# lisa_m.net
KiCad netlist of a schematic drawn in EAGLE
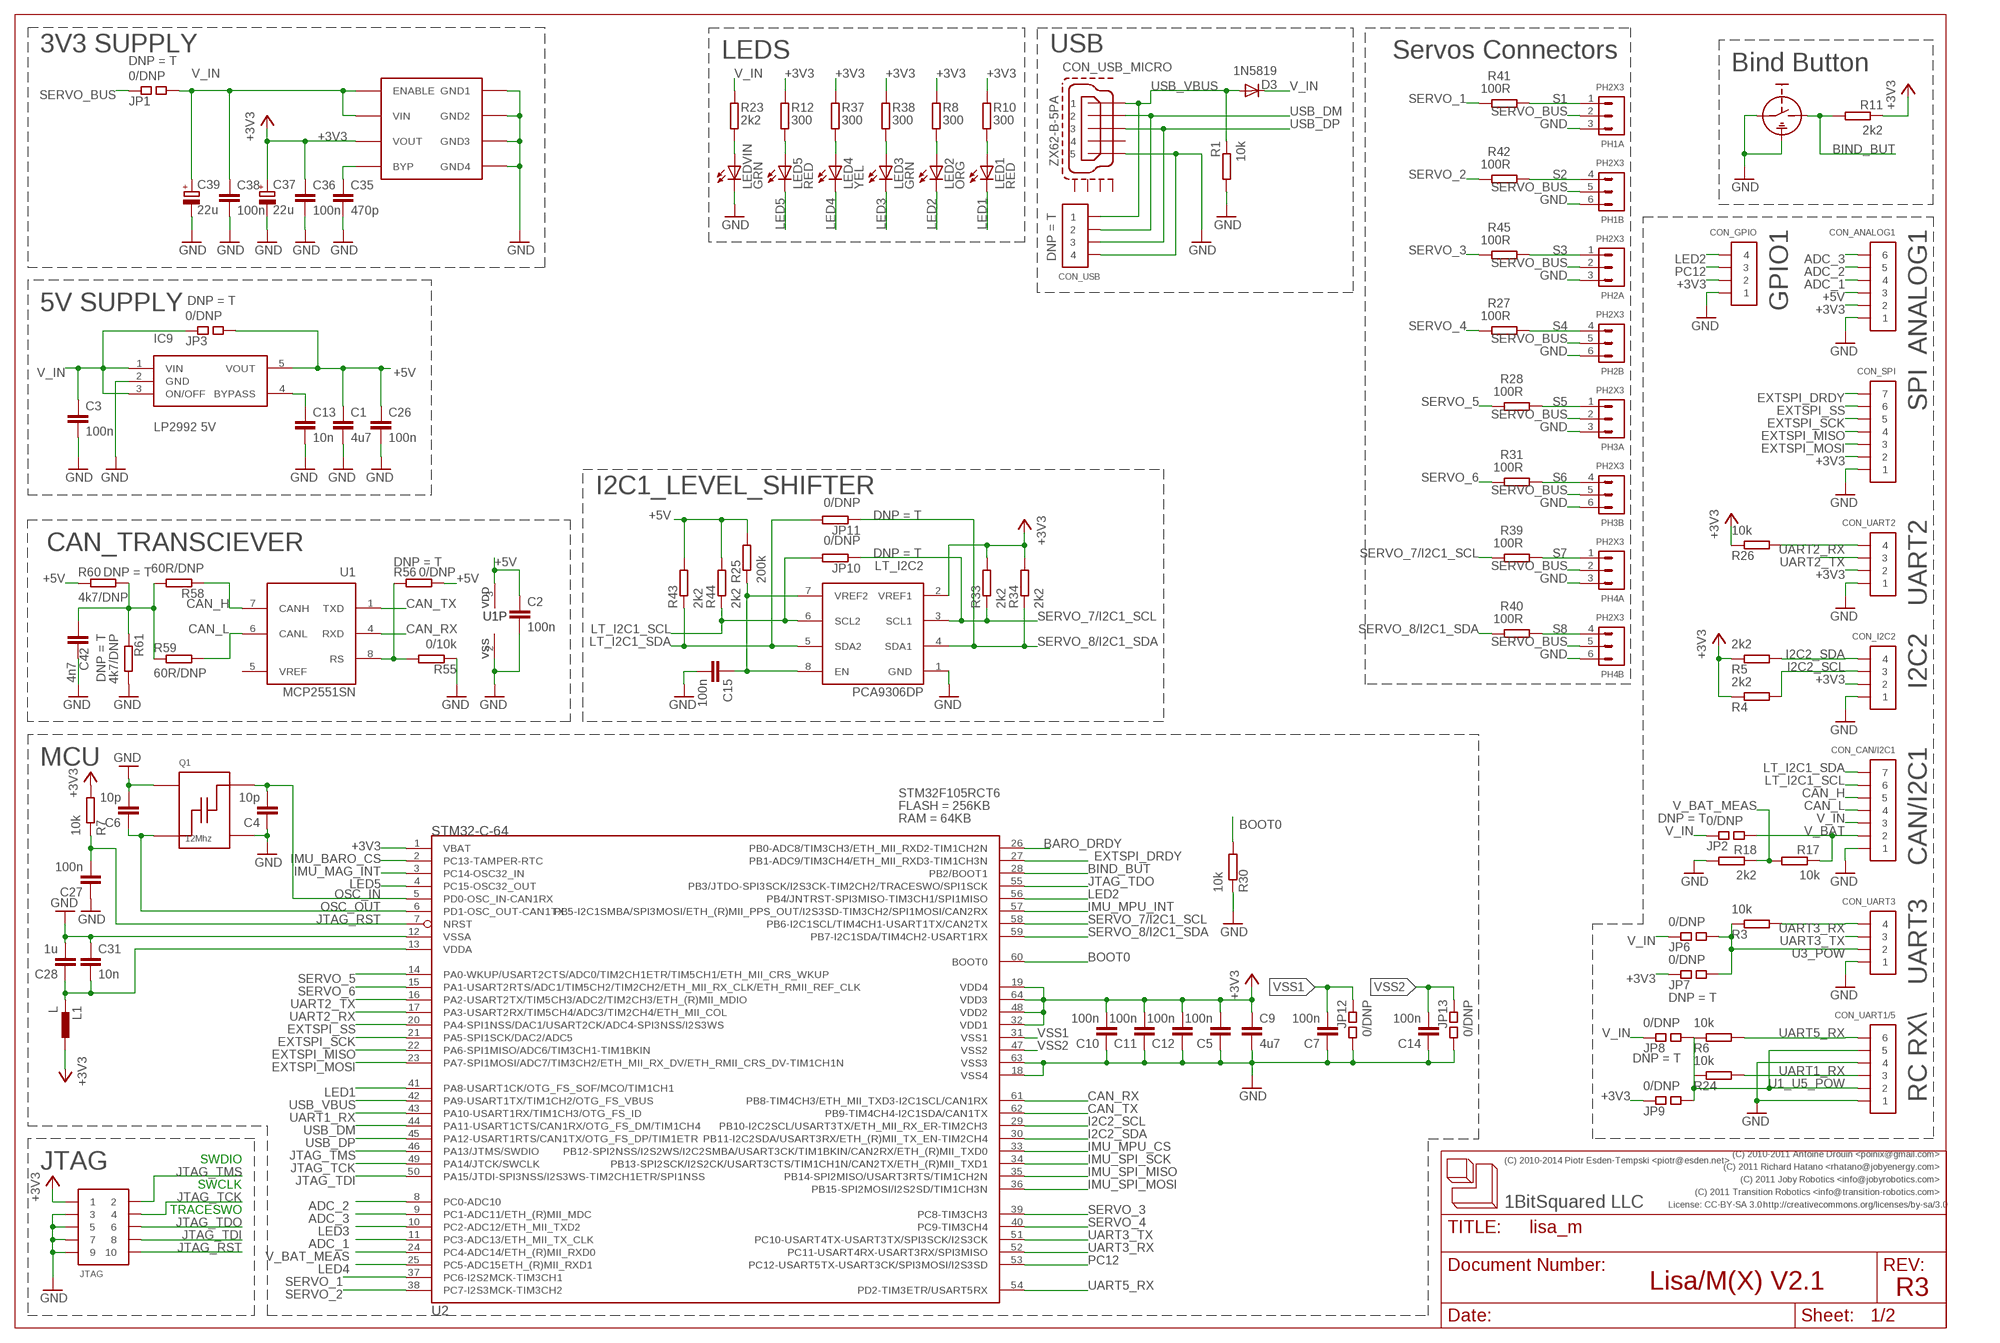
[diagram p0: schematic, sheet 1]
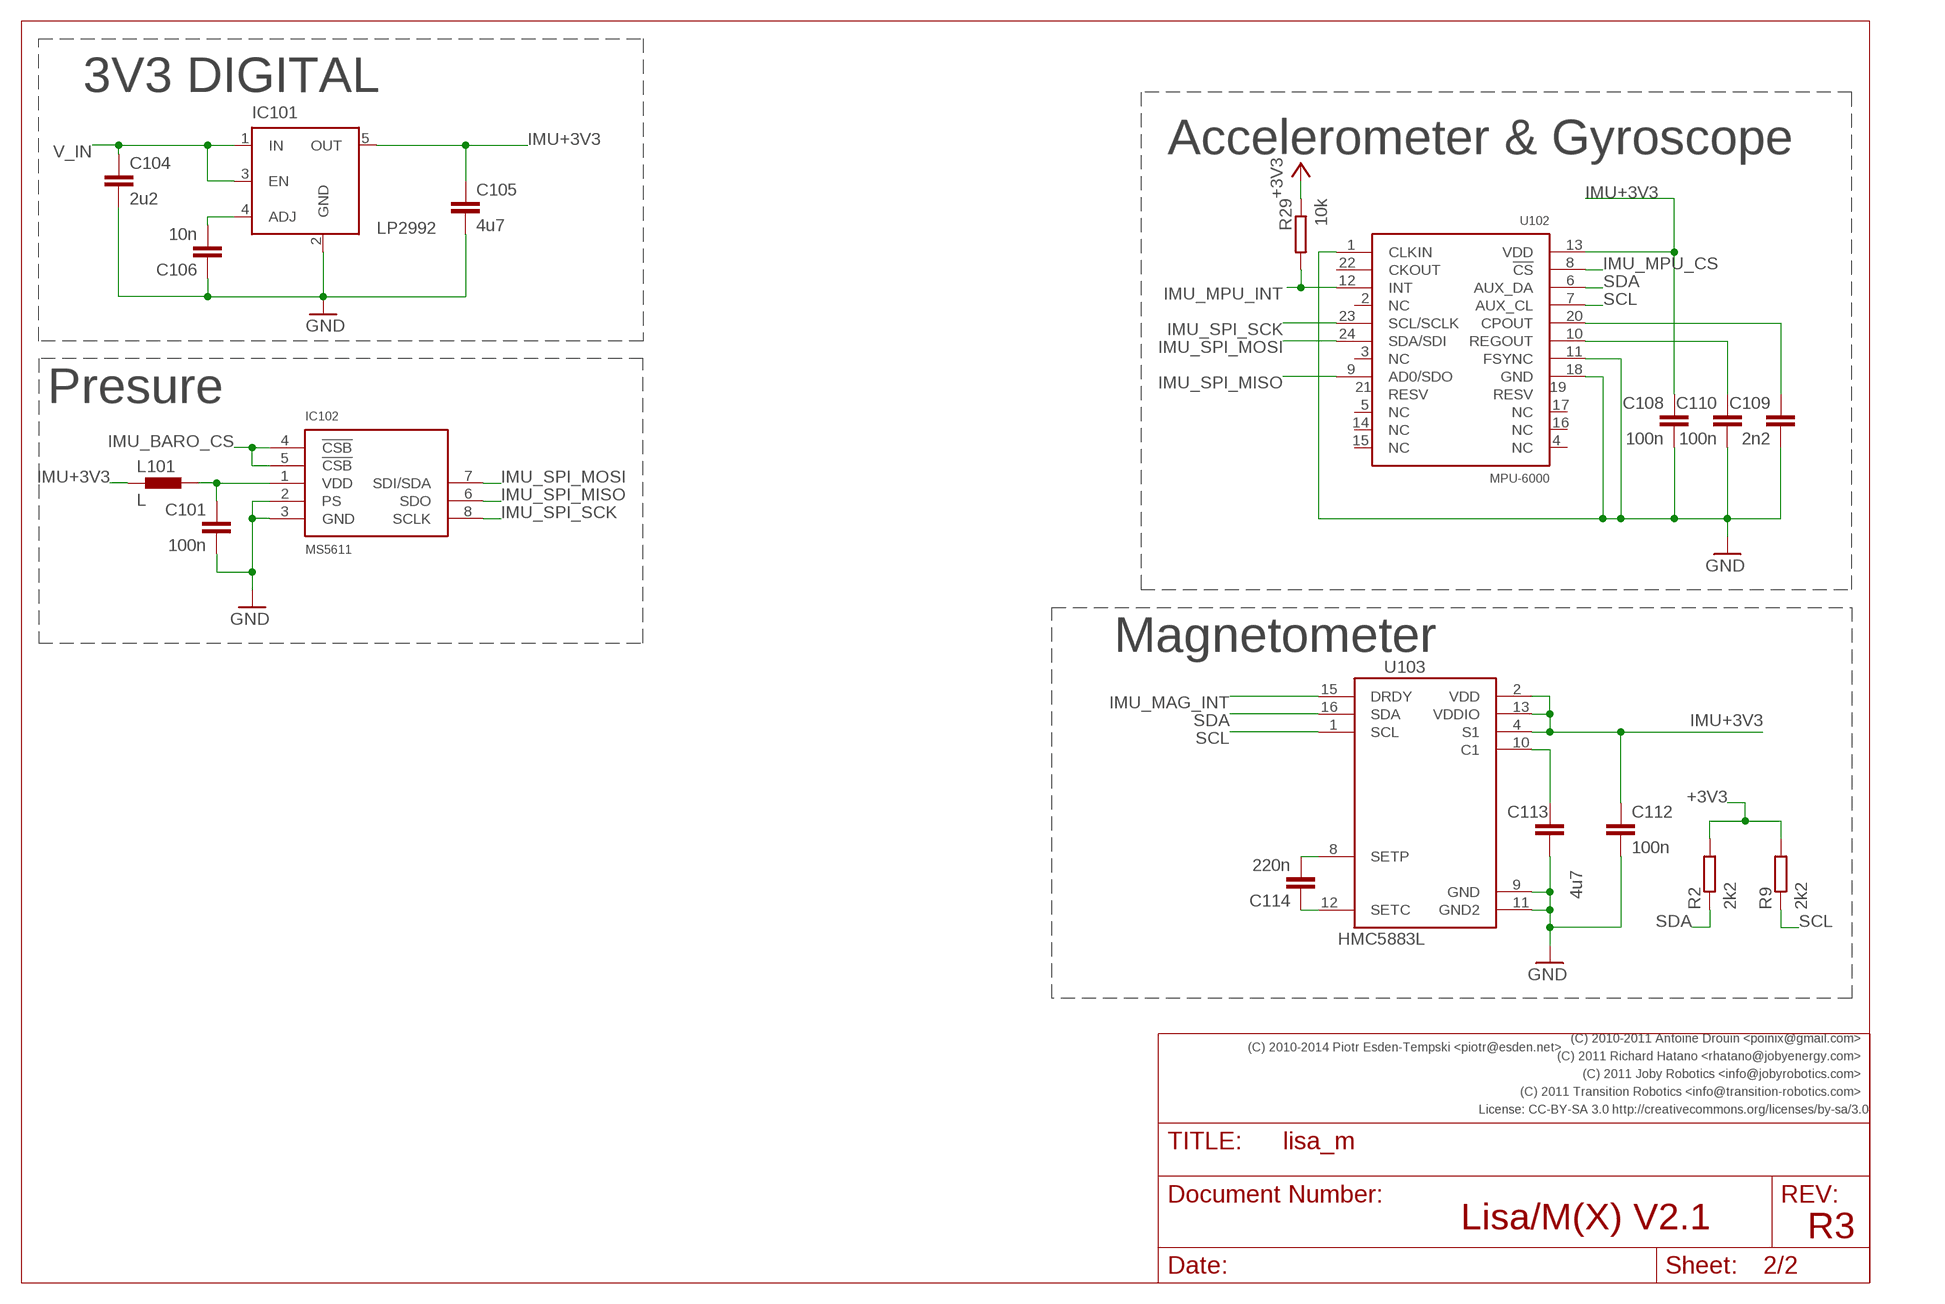
[diagram p1: schematic, sheet 2]

(export (version "E")
  (design (tool "Eeschema 10.0.6"))
  (components
    (comp (ref "C101")
      (value "100n")
      (footprint "eagle-import:0402-CAP")
      (fields (field (name "PARTNO") "cap-cer-0402-100n"))
      (libsource (lib "eagle-import") (part "CAPACITOR-0402"))
    )
    (comp (ref "C104")
      (value "2u2")
      (footprint "eagle-import:0603-CAP")
      (fields (field (name "PARTNO") "cap-cer-0603-2u2"))
      (libsource (lib "eagle-import") (part "CAPACITOR-0603"))
    )
    (comp (ref "C105")
      (value "4u7")
      (footprint "eagle-import:0603-CAP")
      (fields (field (name "PARTNO") "cap-cer-0603-4u7"))
      (libsource (lib "eagle-import") (part "CAPACITOR-0603"))
    )
    (comp (ref "C106")
      (value "10n")
      (footprint "eagle-import:0402-CAP")
      (fields (field (name "PARTNO") "cap-cer-0402-10n"))
      (libsource (lib "eagle-import") (part "CAPACITOR-0402"))
    )
    (comp (ref "C108")
      (value "100n")
      (footprint "eagle-import:0402-CAP")
      (fields (field (name "PARTNO") "cap-cer-0402-100n"))
      (libsource (lib "eagle-import") (part "CAPACITOR-0402"))
    )
    (comp (ref "C109")
      (value "2n2")
      (footprint "eagle-import:0402-CAP")
      (fields (field (name "PARTNO") "cap-cer-0402-2n2"))
      (libsource (lib "eagle-import") (part "CAPACITOR-0402"))
    )
    (comp (ref "C110")
      (value "100n")
      (footprint "eagle-import:0402-CAP")
      (fields (field (name "PARTNO") "cap-cer-0402-100n"))
      (libsource (lib "eagle-import") (part "CAPACITOR-0402"))
    )
    (comp (ref "C112")
      (value "100n")
      (footprint "eagle-import:0402-CAP")
      (fields (field (name "PARTNO") "cap-cer-0402-100n"))
      (libsource (lib "eagle-import") (part "CAPACITOR-0402"))
    )
    (comp (ref "C113")
      (value "4u7")
      (footprint "eagle-import:0603-CAP")
      (fields (field (name "PARTNO") "cap-cer-0603-4u7"))
      (libsource (lib "eagle-import") (part "CAPACITOR-0603"))
    )
    (comp (ref "C114")
      (value "220n")
      (footprint "eagle-import:0603-CAP")
      (fields (field (name "PARTNO") "cap-cer-0603-220n"))
      (libsource (lib "eagle-import") (part "CAPACITOR-0603"))
    )
    (comp (ref "IC101")
      (value "LP2992")
      (footprint "eagle-import:SOT23-5")
      (fields (field (name "PARTNO") "vreg-sot23-5-3v3"))
      (libsource (lib "eagle-import") (part "MIC5219BM5"))
    )
    (comp (ref "IC102")
      (value "MS5611")
      (footprint "eagle-import:QFN-MS5611")
      (fields (field (name "PARTNO") "ic-sensr-ms5611"))
      (libsource (lib "eagle-import") (part "MS5611"))
    )
    (comp (ref "L101")
      (value "L")
      (footprint "eagle-import:0402-IND")
      (fields (field (name "PARTNO") "ferrite-0402-600"))
      (libsource (lib "eagle-import") (part "INDUCTOR-0402"))
    )
    (comp (ref "R2")
      (value "2k2")
      (footprint "eagle-import:0402-RES")
      (fields (field (name "PARTNO") "res-0402-2k2"))
      (libsource (lib "eagle-import") (part "RESISTOR-0402"))
    )
    (comp (ref "R9")
      (value "2k2")
      (footprint "eagle-import:0402-RES")
      (fields (field (name "PARTNO") "res-0402-2k2"))
      (libsource (lib "eagle-import") (part "RESISTOR-0402"))
    )
    (comp (ref "R29")
      (value "10k")
      (footprint "eagle-import:0402-RES")
      (fields (field (name "PARTNO") "res-0402-10k"))
      (libsource (lib "eagle-import") (part "RESISTOR-0402"))
    )
    (comp (ref "U102")
      (value "MPU-6000")
      (footprint "eagle-import:QFN24-NO-PAD")
      (fields (field (name "PARTNO") "ic-sensr-mpu6000"))
      (libsource (lib "eagle-import") (part "MPU-6000"))
    )
    (comp (ref "U103")
      (value "HMC5883L")
      (footprint "eagle-import:LPCC16-HMC5883L")
      (fields (field (name "PARTNO") "ic-sensr-hmc5883l"))
      (libsource (lib "eagle-import") (part "HMC5883L"))
    )
    (comp (ref "C1")
      (value "4u7")
      (footprint "eagle-import:0603-CAP")
      (fields (field (name "PARTNO") "cap-cer-0603-4u7"))
      (libsource (lib "eagle-import") (part "CAPACITOR-0603"))
    )
    (comp (ref "C2")
      (value "100n")
      (footprint "eagle-import:0402-CAP")
      (fields (field (name "PARTNO") "cap-cer-0402-100n"))
      (libsource (lib "eagle-import") (part "CAPACITOR-0402"))
    )
    (comp (ref "C3")
      (value "100n")
      (footprint "eagle-import:0402-CAP")
      (fields (field (name "PARTNO") "cap-cer-0402-100n"))
      (libsource (lib "eagle-import") (part "CAPACITOR-0402"))
    )
    (comp (ref "C4")
      (value "10p")
      (footprint "eagle-import:0402-CAP")
      (fields (field (name "PARTNO") "cap-cer-0402-10p"))
      (libsource (lib "eagle-import") (part "CAPACITOR-0402"))
    )
    (comp (ref "C5")
      (value "100n")
      (footprint "eagle-import:0402-CAP")
      (fields (field (name "PARTNO") "cap-cer-0402-100n"))
      (libsource (lib "eagle-import") (part "CAPACITOR-0402"))
    )
    (comp (ref "C6")
      (value "10p")
      (footprint "eagle-import:0402-CAP")
      (fields (field (name "PARTNO") "cap-cer-0402-10p"))
      (libsource (lib "eagle-import") (part "CAPACITOR-0402"))
    )
    (comp (ref "C7")
      (value "100n")
      (footprint "eagle-import:0402-CAP")
      (fields (field (name "PARTNO") "cap-cer-0402-100n"))
      (libsource (lib "eagle-import") (part "CAPACITOR-0402"))
    )
    (comp (ref "C9")
      (value "4u7")
      (footprint "eagle-import:0603-CAP")
      (fields (field (name "PARTNO") "cap-cer-0603-4u7"))
      (libsource (lib "eagle-import") (part "CAPACITOR-0603"))
    )
    (comp (ref "C10")
      (value "100n")
      (footprint "eagle-import:0402-CAP")
      (fields (field (name "PARTNO") "cap-cer-0402-100n"))
      (libsource (lib "eagle-import") (part "CAPACITOR-0402"))
    )
    (comp (ref "C11")
      (value "100n")
      (footprint "eagle-import:0402-CAP")
      (fields (field (name "PARTNO") "cap-cer-0402-100n"))
      (libsource (lib "eagle-import") (part "CAPACITOR-0402"))
    )
    (comp (ref "C12")
      (value "100n")
      (footprint "eagle-import:0402-CAP")
      (fields (field (name "PARTNO") "cap-cer-0402-100n"))
      (libsource (lib "eagle-import") (part "CAPACITOR-0402"))
    )
    (comp (ref "C13")
      (value "10n")
      (footprint "eagle-import:0402-CAP")
      (fields (field (name "PARTNO") "cap-cer-0402-10n"))
      (libsource (lib "eagle-import") (part "CAPACITOR-0402"))
    )
    (comp (ref "C14")
      (value "100n")
      (footprint "eagle-import:0402-CAP")
      (fields (field (name "PARTNO") "cap-cer-0402-100n"))
      (libsource (lib "eagle-import") (part "CAPACITOR-0402"))
    )
    (comp (ref "C15")
      (value "100n")
      (footprint "eagle-import:0402-CAP")
      (fields (field (name "PARTNO") "cap-cer-0402-100n"))
      (libsource (lib "eagle-import") (part "CAPACITOR-0402"))
    )
    (comp (ref "C26")
      (value "100n")
      (footprint "eagle-import:0402-CAP")
      (fields (field (name "PARTNO") "cap-cer-0402-100n"))
      (libsource (lib "eagle-import") (part "CAPACITOR-0402"))
    )
    (comp (ref "C27")
      (value "100n")
      (footprint "eagle-import:0402-CAP")
      (fields (field (name "PARTNO") "cap-cer-0402-100n"))
      (libsource (lib "eagle-import") (part "CAPACITOR-0402"))
    )
    (comp (ref "C28")
      (value "1u")
      (footprint "eagle-import:0603-CAP")
      (fields (field (name "PARTNO") "cap-cer-0603-1u"))
      (libsource (lib "eagle-import") (part "CAPACITOR-0603"))
    )
    (comp (ref "C31")
      (value "10n")
      (footprint "eagle-import:0402-CAP")
      (fields (field (name "PARTNO") "cap-cer-0402-10n"))
      (libsource (lib "eagle-import") (part "CAPACITOR-0402"))
    )
    (comp (ref "C35")
      (value "470p")
      (footprint "eagle-import:0402-CAP")
      (fields (field (name "PARTNO") "cap-cer-0402-470p"))
      (libsource (lib "eagle-import") (part "CAPACITOR-0402"))
    )
    (comp (ref "C36")
      (value "100n")
      (footprint "eagle-import:0402-CAP")
      (fields (field (name "PARTNO") "cap-cer-0402-100n"))
      (libsource (lib "eagle-import") (part "CAPACITOR-0402"))
    )
    (comp (ref "C37")
      (value "22u")
      (footprint "eagle-import:3528_B")
      (fields (field (name "PARTNO") "cap-tan-B-22u-16v"))
      (libsource (lib "eagle-import") (part "CAPACITOR-POLB"))
    )
    (comp (ref "C38")
      (value "100n")
      (footprint "eagle-import:0402-CAP")
      (fields (field (name "PARTNO") "cap-cer-0402-100n"))
      (libsource (lib "eagle-import") (part "CAPACITOR-0402"))
    )
    (comp (ref "C39")
      (value "22u")
      (footprint "eagle-import:3528_B")
      (fields (field (name "PARTNO") "cap-tan-B-22u-16v"))
      (libsource (lib "eagle-import") (part "CAPACITOR-POLB"))
    )
    (comp (ref "C42")
      (value "4n7")
      (footprint "eagle-import:0603-CAP")
      (fields (field (name "PARTNO") "cap-cer-0603-4n7"))
      (libsource (lib "eagle-import") (part "CAPACITOR-0603"))
    )
    (comp (ref "CON_ANALOG1")
      (value "CONN_6-1-53398")
      (footprint "eagle-import:PB-53398-06")
      (fields (field (name "PARTNO") "conn-picoblade-smd-0.05in-6-vert"))
      (libsource (lib "eagle-import") (part "pel_molex_CONN_6-1-53398"))
    )
    (comp (ref "CON_CAN/I2C1")
      (value "CONN_7-1-53398")
      (footprint "eagle-import:PB-53398-07")
      (fields (field (name "PARTNO") "conn-picoblade-smd-0.05in-7-vert"))
      (libsource (lib "eagle-import") (part "CONN_7-1-53398"))
    )
    (comp (ref "CON_GPIO")
      (value "CONN_4-1-53398")
      (footprint "eagle-import:PB-53398-04")
      (fields (field (name "PARTNO") "conn-picoblade-smd-0.05in-4-vert"))
      (libsource (lib "eagle-import") (part "CONN_4-1-53398"))
    )
    (comp (ref "CON_I2C2")
      (value "CONN_4-1-53398")
      (footprint "eagle-import:PB-53398-04")
      (fields (field (name "PARTNO") "conn-picoblade-smd-0.05in-4-vert"))
      (libsource (lib "eagle-import") (part "CONN_4-1-53398"))
    )
    (comp (ref "CON_SPI")
      (value "CONN_7-1-53398")
      (footprint "eagle-import:PB-53398-07")
      (fields (field (name "PARTNO") "conn-picoblade-smd-0.05in-7-vert"))
      (libsource (lib "eagle-import") (part "CONN_7-1-53398"))
    )
    (comp (ref "CON_UART1/5")
      (value "CONN_6-1PB-53398-06_SMALL")
      (footprint "eagle-import:PB-53398-06")
      (fields (field (name "PARTNO") "conn-picoblade-smd-0.05in-6-vert"))
      (libsource (lib "eagle-import") (part "CONN_6-1PB-53398-06_SMALL"))
    )
    (comp (ref "CON_UART2")
      (value "CONN_4-1-53398")
      (footprint "eagle-import:PB-53398-04")
      (fields (field (name "PARTNO") "conn-picoblade-smd-0.05in-4-vert"))
      (libsource (lib "eagle-import") (part "CONN_4-1-53398"))
    )
    (comp (ref "CON_UART3")
      (value "CONN_4-1-53398")
      (footprint "eagle-import:PB-53398-04")
      (fields (field (name "PARTNO") "conn-picoblade-smd-0.05in-4-vert"))
      (libsource (lib "eagle-import") (part "CONN_4-1-53398"))
    )
    (comp (ref "CON_USB")
      (value "CONN_4-1-53047")
      (footprint "eagle-import:PB-53047-04")
      (fields (field (name "DNP") "T") (field (name "PARTNO") "conn-picoblade-th-0.05in-4-vert"))
      (libsource (lib "eagle-import") (part "CONN_4-1-53047"))
    )
    (comp (ref "CON_USB_MICRO")
      (value "ZX62-B-5PA")
      (footprint "eagle-import:ZX62-B-5PA")
      (fields (field (name "PARTNO") "conn-smd-usb-micro-b"))
      (libsource (lib "eagle-import") (part "ZX62-B-5PA"))
    )
    (comp (ref "D3")
      (value "1N5819")
      (footprint "eagle-import:0603-DIO")
      (fields (field (name "PARTNO") "diode-schottky-0603"))
      (libsource (lib "eagle-import") (part "DIODE-0603"))
    )
    (comp (ref "IC9")
      (value "LP2992 5V")
      (footprint "eagle-import:SOT23-5")
      (fields (field (name "PARTNO") "vreg-sot-23-5-5v"))
      (libsource (lib "eagle-import") (part "LP2992"))
    )
    (comp (ref "JP1")
      (value "0/DNP")
      (footprint "eagle-import:0402-SQJMP")
      (fields (field (name "DNP") "T") (field (name "PARTNO") "res-0402-0"))
      (libsource (lib "eagle-import") (part "SQ_JMP-0402"))
    )
    (comp (ref "JP2")
      (value "0/DNP")
      (footprint "eagle-import:0402-SQJMP")
      (fields (field (name "DNP") "T") (field (name "PARTNO") "res-0402-0"))
      (libsource (lib "eagle-import") (part "SQ_JMP-0402"))
    )
    (comp (ref "JP3")
      (value "0/DNP")
      (footprint "eagle-import:0402-SQJMP")
      (fields (field (name "DNP") "T") (field (name "PARTNO") "res-0402-0"))
      (libsource (lib "eagle-import") (part "SQ_JMP-0402"))
    )
    (comp (ref "JP6")
      (value "0/DNP")
      (footprint "eagle-import:0402-SQJMP")
      (fields (field (name "PARTNO") "res-0402-0"))
      (libsource (lib "eagle-import") (part "SQ_JMP-0402"))
    )
    (comp (ref "JP7")
      (value "0/DNP")
      (footprint "eagle-import:0402-SQJMP")
      (fields (field (name "DNP") "T") (field (name "PARTNO") "res-0402-0"))
      (libsource (lib "eagle-import") (part "SQ_JMP-0402"))
    )
    (comp (ref "JP8")
      (value "0/DNP")
      (footprint "eagle-import:0402-SQJMP")
      (fields (field (name "DNP") "T") (field (name "PARTNO") "res-0402-0"))
      (libsource (lib "eagle-import") (part "SQ_JMP-0402"))
    )
    (comp (ref "JP9")
      (value "0/DNP")
      (footprint "eagle-import:0402-SQJMP")
      (fields (field (name "PARTNO") "res-0402-0"))
      (libsource (lib "eagle-import") (part "SQ_JMP-0402"))
    )
    (comp (ref "JP10")
      (value "0/DNP")
      (footprint "eagle-import:0603-RES")
      (fields (field (name "DNP") "T") (field (name "PARTNO") "res-0603-0"))
      (libsource (lib "eagle-import") (part "RESISTOR-0603"))
    )
    (comp (ref "JP11")
      (value "0/DNP")
      (footprint "eagle-import:0603-RES")
      (fields (field (name "DNP") "T") (field (name "PARTNO") "res-0603-0"))
      (libsource (lib "eagle-import") (part "RESISTOR-0603"))
    )
    (comp (ref "JP12")
      (value "0/DNP")
      (footprint "eagle-import:0402-SQJMP")
      (fields (field (name "PARTNO") "res-0402-0"))
      (libsource (lib "eagle-import") (part "SQ_JMP-0402"))
    )
    (comp (ref "JP13")
      (value "0/DNP")
      (footprint "eagle-import:0402-SQJMP")
      (fields (field (name "PARTNO") "res-0402-0"))
      (libsource (lib "eagle-import") (part "SQ_JMP-0402"))
    )
    (comp (ref "JTAG")
      (value "PIN_HDR_EDG_1.27MM_5-2")
      (footprint "eagle-import:FTSH-105-DV")
      (fields (field (name "PARTNO") "conn-smd-0.05in-5-2"))
      (libsource (lib "eagle-import") (part "CONN_5-2-FTSH-V"))
    )
    (comp (ref "L1")
      (value "L")
      (footprint "eagle-import:0402-IND")
      (fields (field (name "PARTNO") "ferrite-0402-600"))
      (libsource (lib "eagle-import") (part "INDUCTOR-0402"))
    )
    (comp (ref "LED1")
      (value "RED")
      (footprint "eagle-import:0402-LED")
      (fields (field (name "PARTNO") "led-0402-red"))
      (libsource (lib "eagle-import") (part "LED-0402"))
    )
    (comp (ref "LED2")
      (value "ORG")
      (footprint "eagle-import:0402-LED")
      (fields (field (name "PARTNO") "led-0402-org"))
      (libsource (lib "eagle-import") (part "LED-0402"))
    )
    (comp (ref "LED3")
      (value "GRN")
      (footprint "eagle-import:0402-LED")
      (fields (field (name "PARTNO") "led-0402-grn"))
      (libsource (lib "eagle-import") (part "LED-0402"))
    )
    (comp (ref "LED4")
      (value "YEL")
      (footprint "eagle-import:0402-LED")
      (fields (field (name "PARTNO") "led-0402-yel"))
      (libsource (lib "eagle-import") (part "LED-0402"))
    )
    (comp (ref "LED5")
      (value "RED")
      (footprint "eagle-import:0402-LED")
      (fields (field (name "PARTNO") "led-0402-grn"))
      (libsource (lib "eagle-import") (part "LED-0402"))
    )
    (comp (ref "LEDVIN")
      (value "GRN")
      (footprint "eagle-import:0402-LED")
      (fields (field (name "PARTNO") "led-0402-grn"))
      (libsource (lib "eagle-import") (part "LED-0402"))
    )
    (comp (ref "LT_I2C2")
      (value "PCA9306DP")
      (footprint "eagle-import:TSSOP_B3")
      (fields (field (name "PARTNO") "ic-tssop8-level-trans"))
      (libsource (lib "eagle-import") (part "PCA9306DP"))
    )
    (comp (ref "PH1")
      (value "PH2X3")
      (footprint "eagle-import:PH010-2-3")
      (libsource (lib "eagle-import") (part "PH2X3"))
    )
    (comp (ref "PH2")
      (value "PH2X3")
      (footprint "eagle-import:PH010-2-3")
      (libsource (lib "eagle-import") (part "PH2X3"))
    )
    (comp (ref "PH3")
      (value "PH2X3")
      (footprint "eagle-import:PH010-2-3")
      (libsource (lib "eagle-import") (part "PH2X3"))
    )
    (comp (ref "PH4")
      (value "PH2X3")
      (footprint "eagle-import:PH010-2-3")
      (libsource (lib "eagle-import") (part "PH2X3"))
    )
    (comp (ref "Q1")
      (value "12Mhz")
      (footprint "eagle-import:ABM8")
      (fields (field (name "PARTNO") "xtal-abm8-12mhz"))
      (libsource (lib "eagle-import") (part "ABM8"))
    )
    (comp (ref "R1")
      (value "10k")
      (footprint "eagle-import:0402-RES")
      (fields (field (name "PARTNO") "res-0402-10k"))
      (libsource (lib "eagle-import") (part "RESISTOR-0402"))
    )
    (comp (ref "R3")
      (value "10k")
      (footprint "eagle-import:0402-RES")
      (fields (field (name "PARTNO") "res-0402-10k"))
      (libsource (lib "eagle-import") (part "RESISTOR-0402"))
    )
    (comp (ref "R4")
      (value "2k2")
      (footprint "eagle-import:0402-RES")
      (fields (field (name "PARTNO") "res-0402-2k2"))
      (libsource (lib "eagle-import") (part "RESISTOR-0402"))
    )
    (comp (ref "R5")
      (value "2k2")
      (footprint "eagle-import:0402-RES")
      (fields (field (name "PARTNO") "res-0402-2k2"))
      (libsource (lib "eagle-import") (part "RESISTOR-0402"))
    )
    (comp (ref "R6")
      (value "10k")
      (footprint "eagle-import:0402-RES")
      (fields (field (name "PARTNO") "res-0402-10k"))
      (libsource (lib "eagle-import") (part "RESISTOR-0402"))
    )
    (comp (ref "R7")
      (value "10k")
      (footprint "eagle-import:0402-RES")
      (fields (field (name "PARTNO") "res-0402-10k"))
      (libsource (lib "eagle-import") (part "RESISTOR-0402"))
    )
    (comp (ref "R8")
      (value "300")
      (footprint "eagle-import:0402-RES")
      (fields (field (name "PARTNO") "res-0402-300"))
      (libsource (lib "eagle-import") (part "RESISTOR-0402"))
    )
    (comp (ref "R10")
      (value "300")
      (footprint "eagle-import:0402-RES")
      (fields (field (name "PARTNO") "res-0402-300"))
      (libsource (lib "eagle-import") (part "RESISTOR-0402"))
    )
    (comp (ref "R11")
      (value "2k2")
      (footprint "eagle-import:0402-RES")
      (fields (field (name "PARTNO") "res-0402-2k2"))
      (libsource (lib "eagle-import") (part "RESISTOR-0402"))
    )
    (comp (ref "R12")
      (value "300")
      (footprint "eagle-import:0402-RES")
      (fields (field (name "PARTNO") "res-0402-300"))
      (libsource (lib "eagle-import") (part "RESISTOR-0402"))
    )
    (comp (ref "R17")
      (value "10k")
      (footprint "eagle-import:0402-RES")
      (fields (field (name "PARTNO") "res-0402-10k"))
      (libsource (lib "eagle-import") (part "RESISTOR-0402"))
    )
    (comp (ref "R18")
      (value "2k2")
      (footprint "eagle-import:0402-RES")
      (fields (field (name "PARTNO") "res-0402-2k2"))
      (libsource (lib "eagle-import") (part "RESISTOR-0402"))
    )
    (comp (ref "R23")
      (value "2k2")
      (footprint "eagle-import:0402-RES")
      (fields (field (name "PARTNO") "res-0402-2k2"))
      (libsource (lib "eagle-import") (part "RESISTOR-0402"))
    )
    (comp (ref "R24")
      (value "10k")
      (footprint "eagle-import:0402-RES")
      (fields (field (name "PARTNO") "res-0402-10k"))
      (libsource (lib "eagle-import") (part "RESISTOR-0402"))
    )
    (comp (ref "R25")
      (value "200k")
      (footprint "eagle-import:0402-RES")
      (fields (field (name "PARTNO") "res-0402-200k"))
      (libsource (lib "eagle-import") (part "RESISTOR-0402"))
    )
    (comp (ref "R26")
      (value "10k")
      (footprint "eagle-import:0402-RES")
      (fields (field (name "PARTNO") "res-0402-10k"))
      (libsource (lib "eagle-import") (part "RESISTOR-0402"))
    )
    (comp (ref "R27")
      (value "100R")
      (footprint "eagle-import:0402-RES")
      (fields (field (name "PARTNO") "res-0402-100"))
      (libsource (lib "eagle-import") (part "RESISTOR-0402"))
    )
    (comp (ref "R28")
      (value "100R")
      (footprint "eagle-import:0402-RES")
      (fields (field (name "PARTNO") "res-0402-100"))
      (libsource (lib "eagle-import") (part "RESISTOR-0402"))
    )
    (comp (ref "R30")
      (value "10k")
      (footprint "eagle-import:0402-RES")
      (fields (field (name "PARTNO") "res-0402-10k"))
      (libsource (lib "eagle-import") (part "RESISTOR-0402"))
    )
    (comp (ref "R31")
      (value "100R")
      (footprint "eagle-import:0402-RES")
      (fields (field (name "PARTNO") "res-0402-100"))
      (libsource (lib "eagle-import") (part "RESISTOR-0402"))
    )
    (comp (ref "R33")
      (value "2k2")
      (footprint "eagle-import:0402-RES")
      (fields (field (name "PARTNO") "res-0402-2k2"))
      (libsource (lib "eagle-import") (part "RESISTOR-0402"))
    )
    (comp (ref "R34")
      (value "2k2")
      (footprint "eagle-import:0402-RES")
      (fields (field (name "PARTNO") "res-0402-2k2"))
      (libsource (lib "eagle-import") (part "RESISTOR-0402"))
    )
    (comp (ref "R37")
      (value "300")
      (footprint "eagle-import:0402-RES")
      (fields (field (name "PARTNO") "res-0402-300"))
      (libsource (lib "eagle-import") (part "RESISTOR-0402"))
    )
    (comp (ref "R38")
      (value "300")
      (footprint "eagle-import:0402-RES")
      (fields (field (name "PARTNO") "res-0402-300"))
      (libsource (lib "eagle-import") (part "RESISTOR-0402"))
    )
    (comp (ref "R39")
      (value "100R")
      (footprint "eagle-import:0402-RES")
      (fields (field (name "PARTNO") "res-0402-100"))
      (libsource (lib "eagle-import") (part "RESISTOR-0402"))
    )
    (comp (ref "R40")
      (value "100R")
      (footprint "eagle-import:0402-RES")
      (fields (field (name "PARTNO") "res-0402-100"))
      (libsource (lib "eagle-import") (part "RESISTOR-0402"))
    )
    (comp (ref "R41")
      (value "100R")
      (footprint "eagle-import:0402-RES")
      (fields (field (name "PARTNO") "res-0402-100"))
      (libsource (lib "eagle-import") (part "RESISTOR-0402"))
    )
    (comp (ref "R42")
      (value "100R")
      (footprint "eagle-import:0402-RES")
      (fields (field (name "PARTNO") "res-0402-100"))
      (libsource (lib "eagle-import") (part "RESISTOR-0402"))
    )
    (comp (ref "R43")
      (value "2k2")
      (footprint "eagle-import:0402-RES")
      (fields (field (name "PARTNO") "res-0402-2k2"))
      (libsource (lib "eagle-import") (part "RESISTOR-0402"))
    )
    (comp (ref "R44")
      (value "2k2")
      (footprint "eagle-import:0402-RES")
      (fields (field (name "PARTNO") "res-0402-2k2"))
      (libsource (lib "eagle-import") (part "RESISTOR-0402"))
    )
    (comp (ref "R45")
      (value "100R")
      (footprint "eagle-import:0402-RES")
      (fields (field (name "PARTNO") "res-0402-100"))
      (libsource (lib "eagle-import") (part "RESISTOR-0402"))
    )
    (comp (ref "R55")
      (value "0/10k")
      (footprint "eagle-import:0402-RES")
      (fields (field (name "PARTNO") "res-0402-10k"))
      (libsource (lib "eagle-import") (part "RESISTOR-0402"))
    )
    (comp (ref "R56")
      (value "0/DNP")
      (footprint "eagle-import:0402-RES")
      (fields (field (name "DNP") "T") (field (name "PARTNO") "res-0402-0"))
      (libsource (lib "eagle-import") (part "RESISTOR-0402"))
    )
    (comp (ref "R58")
      (value "60R/DNP")
      (footprint "eagle-import:0402-RES")
      (fields (field (name "PARTNO") "res-0402-60.4"))
      (libsource (lib "eagle-import") (part "RESISTOR-0402"))
    )
    (comp (ref "R59")
      (value "60R/DNP")
      (footprint "eagle-import:0402-RES")
      (fields (field (name "PARTNO") "res-0402-60.4"))
      (libsource (lib "eagle-import") (part "RESISTOR-0402"))
    )
    (comp (ref "R60")
      (value "4k7/DNP")
      (footprint "eagle-import:0402-RES")
      (fields (field (name "DNP") "T") (field (name "PARTNO") "res-0402-4k7"))
      (libsource (lib "eagle-import") (part "RESISTOR-0402"))
    )
    (comp (ref "R61")
      (value "4k7/DNP")
      (footprint "eagle-import:0402-RES")
      (fields (field (name "DNP") "T") (field (name "PARTNO") "res-0402-4k7"))
      (libsource (lib "eagle-import") (part "RESISTOR-0402"))
    )
    (comp (ref "SW1")
      (value "MICROTACT_GND")
      (footprint "eagle-import:MICROTACT_GND")
      (fields (field (name "PARTNO") "sw-tact-top-gnd-3.0-2.5"))
      (libsource (lib "eagle-import") (part "MICROTACT_GND"))
    )
    (comp (ref "U1")
      (value "MCP2551SN")
      (footprint "eagle-import:SO-08")
      (fields (field (name "PARTNO") "ic-so8-can"))
      (libsource (lib "eagle-import") (part "MCP2551SN"))
    )
    (comp (ref "U2")
      (value "STM32-C-64")
      (footprint "eagle-import:LQFP64")
      (fields
        (field (name "FLASH") "256KB")
        (field (name "PARTNO") "ic-mcu-stm32f415rgt6")
        (field (name "PART_NR") "STM32F105RCT6")
        (field (name "RAM") "64KB")
      )
      (libsource (lib "eagle-import") (part "STM32-C-64"))
    )
    (comp (ref "VREG1")
      (value "MIC5209")
      (footprint "eagle-import:SOIC8")
      (fields (field (name "PARTNO") "vreg-so8-3v3"))
      (libsource (lib "eagle-import") (part "MIC5209"))
    )
  )
  (nets
    (net (code "1") (name "+3V3") (class "Default")
      (node (ref "C10") (pin "P$2") (pinfunction "2_P$2") (pintype "passive"))
      (node (ref "C11") (pin "P$2") (pinfunction "2_P$2") (pintype "passive"))
      (node (ref "C12") (pin "P$2") (pinfunction "2_P$2") (pintype "passive"))
      (node (ref "C36") (pin "P$1") (pinfunction "1_P$1") (pintype "passive"))
      (node (ref "C37") (pin "+") (pinfunction "+_+") (pintype "passive"))
      (node (ref "C5") (pin "P$2") (pinfunction "2_P$2") (pintype "passive"))
      (node (ref "C9") (pin "P$1") (pinfunction "1_P$1") (pintype "passive"))
      (node (ref "CON_ANALOG1") (pin "2") (pinfunction "2_2") (pintype "bidirectional"))
      (node (ref "CON_GPIO") (pin "2") (pinfunction "2_2") (pintype "bidirectional"))
      (node (ref "CON_I2C2") (pin "2") (pinfunction "2_2") (pintype "bidirectional"))
      (node (ref "CON_SPI") (pin "2") (pinfunction "2_2") (pintype "bidirectional"))
      (node (ref "CON_UART2") (pin "2") (pinfunction "2_2") (pintype "bidirectional"))
      (node (ref "JP7") (pin "P$1") (pinfunction "1_P$1") (pintype "passive"))
      (node (ref "JP9") (pin "P$1") (pinfunction "1_P$1") (pintype "passive"))
      (node (ref "JTAG") (pin "1") (pinfunction "1_1") (pintype "bidirectional"))
      (node (ref "L1") (pin "P$1") (pinfunction "1_P$1") (pintype "passive"))
      (node (ref "LT_I2C2") (pin "2") (pinfunction "VREF1_2") (pintype "bidirectional"))
      (node (ref "R10") (pin "P$2") (pinfunction "2_P$2") (pintype "passive"))
      (node (ref "R11") (pin "P$1") (pinfunction "1_P$1") (pintype "passive"))
      (node (ref "R12") (pin "P$2") (pinfunction "2_P$2") (pintype "passive"))
      (node (ref "R2") (pin "P$2") (pinfunction "2_P$2") (pintype "passive"))
      (node (ref "R26") (pin "P$1") (pinfunction "1_P$1") (pintype "passive"))
      (node (ref "R29") (pin "P$1") (pinfunction "1_P$1") (pintype "passive"))
      (node (ref "R33") (pin "P$2") (pinfunction "2_P$2") (pintype "passive"))
      (node (ref "R34") (pin "P$2") (pinfunction "2_P$2") (pintype "passive"))
      (node (ref "R37") (pin "P$2") (pinfunction "2_P$2") (pintype "passive"))
      (node (ref "R38") (pin "P$2") (pinfunction "2_P$2") (pintype "passive"))
      (node (ref "R4") (pin "P$1") (pinfunction "1_P$1") (pintype "passive"))
      (node (ref "R5") (pin "P$1") (pinfunction "1_P$1") (pintype "passive"))
      (node (ref "R7") (pin "P$2") (pinfunction "2_P$2") (pintype "passive"))
      (node (ref "R8") (pin "P$2") (pinfunction "2_P$2") (pintype "passive"))
      (node (ref "R9") (pin "P$2") (pinfunction "2_P$2") (pintype "passive"))
      (node (ref "U2") (pin "1") (pinfunction "VBAT_1") (pintype "power_in"))
      (node (ref "U2") (pin "19") (pinfunction "VDD4_19") (pintype "bidirectional"))
      (node (ref "U2") (pin "32") (pinfunction "VDD1_32") (pintype "power_in"))
      (node (ref "U2") (pin "48") (pinfunction "VDD2_48") (pintype "power_in"))
      (node (ref "U2") (pin "64") (pinfunction "VDD3_64") (pintype "power_in"))
      (node (ref "VREG1") (pin "3") (pinfunction "VOUT_3") (pintype "bidirectional"))
    )
    (net (code "2") (name "+5V") (class "Default")
      (node (ref "C1") (pin "P$1") (pinfunction "1_P$1") (pintype "passive"))
      (node (ref "C2") (pin "P$1") (pinfunction "1_P$1") (pintype "passive"))
      (node (ref "C26") (pin "P$1") (pinfunction "1_P$1") (pintype "passive"))
      (node (ref "CON_ANALOG1") (pin "3") (pinfunction "3_3") (pintype "bidirectional"))
      (node (ref "IC9") (pin "5") (pinfunction "VOUT_5") (pintype "bidirectional"))
      (node (ref "JP3") (pin "P$2") (pinfunction "2_P$2") (pintype "passive"))
      (node (ref "R25") (pin "P$2") (pinfunction "2_P$2") (pintype "passive"))
      (node (ref "R43") (pin "P$2") (pinfunction "2_P$2") (pintype "passive"))
      (node (ref "R44") (pin "P$2") (pinfunction "2_P$2") (pintype "passive"))
      (node (ref "R56") (pin "P$2") (pinfunction "2_P$2") (pintype "passive"))
      (node (ref "R60") (pin "P$1") (pinfunction "1_P$1") (pintype "passive"))
      (node (ref "U1") (pin "3") (pinfunction "VDD_3") (pintype "power_in"))
    )
    (net (code "3") (name "ADC_1") (class "Default")
      (node (ref "CON_ANALOG1") (pin "4") (pinfunction "4_4") (pintype "bidirectional"))
      (node (ref "U2") (pin "11") (pinfunction "PC3-ADC13/ETH_MII_TX_CLK_11") (pintype "bidirectional"))
    )
    (net (code "4") (name "ADC_2") (class "Default")
      (node (ref "CON_ANALOG1") (pin "5") (pinfunction "5_5") (pintype "bidirectional"))
      (node (ref "U2") (pin "8") (pinfunction "PC0-ADC10_8") (pintype "bidirectional"))
    )
    (net (code "5") (name "ADC_3") (class "Default")
      (node (ref "CON_ANALOG1") (pin "6") (pinfunction "6_6") (pintype "bidirectional"))
      (node (ref "U2") (pin "9") (pinfunction "PC1-ADC11/ETH_(R)MII_MDC_9") (pintype "bidirectional"))
    )
    (net (code "6") (name "BARO_DRDY") (class "Default")
      (node (ref "U2") (pin "26") (pinfunction "PB0-ADC8/TIM3CH3/ETH_MII_RXD2-TIM1CH2N_26") (pintype "bidirectional"))
    )
    (net (code "7") (name "BIND_BUT") (class "Default")
      (node (ref "R11") (pin "P$2") (pinfunction "2_P$2") (pintype "passive"))
      (node (ref "SW1") (pin "2") (pinfunction "2_2") (pintype "bidirectional"))
      (node (ref "U2") (pin "28") (pinfunction "PB2/BOOT1_28") (pintype "bidirectional"))
    )
    (net (code "8") (name "BOOT0") (class "Default")
      (node (ref "R30") (pin "P$2") (pinfunction "2_P$2") (pintype "passive"))
      (node (ref "U2") (pin "60") (pinfunction "BOOT0_60") (pintype "input"))
    )
    (net (code "9") (name "CAN_H") (class "Default")
      (node (ref "CON_CAN/I2C1") (pin "5") (pinfunction "5_5") (pintype "bidirectional"))
      (node (ref "R58") (pin "P$1") (pinfunction "1_P$1") (pintype "passive"))
      (node (ref "U1") (pin "7") (pinfunction "CANH_7") (pintype "bidirectional"))
    )
    (net (code "10") (name "CAN_L") (class "Default")
      (node (ref "CON_CAN/I2C1") (pin "4") (pinfunction "4_4") (pintype "bidirectional"))
      (node (ref "R59") (pin "P$2") (pinfunction "2_P$2") (pintype "passive"))
      (node (ref "U1") (pin "6") (pinfunction "CANL_6") (pintype "bidirectional"))
    )
    (net (code "11") (name "CAN_RX") (class "Default")
      (node (ref "U1") (pin "4") (pinfunction "RXD_4") (pintype "output"))
      (node (ref "U2") (pin "61") (pinfunction "PB8-TIM4CH3/ETH_MII_TXD3-I2C1SCL/CAN1RX_61") (pintype "bidirectional"))
    )
    (net (code "12") (name "CAN_TX") (class "Default")
      (node (ref "U1") (pin "1") (pinfunction "TXD_1") (pintype "input"))
      (node (ref "U2") (pin "62") (pinfunction "PB9-TIM4CH4-I2C1SDA/CAN1TX_62") (pintype "bidirectional"))
    )
    (net (code "13") (name "EXTSPI_DRDY") (class "Default")
      (node (ref "CON_SPI") (pin "7") (pinfunction "7_7") (pintype "bidirectional"))
      (node (ref "U2") (pin "27") (pinfunction "PB1-ADC9/TIM3CH4/ETH_MII_RXD3-TIM1CH3N_27") (pintype "bidirectional"))
    )
    (net (code "14") (name "EXTSPI_MISO") (class "Default")
      (node (ref "CON_SPI") (pin "4") (pinfunction "4_4") (pintype "bidirectional"))
      (node (ref "U2") (pin "22") (pinfunction "PA6-SPI1MISO/ADC6/TIM3CH1-TIM1BKIN_22") (pintype "bidirectional"))
    )
    (net (code "15") (name "EXTSPI_MOSI") (class "Default")
      (node (ref "CON_SPI") (pin "3") (pinfunction "3_3") (pintype "bidirectional"))
      (node (ref "U2") (pin "23") (pinfunction "PA7-SPI1MOSI/ADC7/TIM3CH2/ETH_MII_RX_DV/ETH_RMII_CRS_DV-TIM1CH1N_23") (pintype "bidirectional"))
    )
    (net (code "16") (name "EXTSPI_SCK") (class "Default")
      (node (ref "CON_SPI") (pin "5") (pinfunction "5_5") (pintype "bidirectional"))
      (node (ref "U2") (pin "21") (pinfunction "PA5-SPI1SCK/DAC2/ADC5_21") (pintype "bidirectional"))
    )
    (net (code "17") (name "EXTSPI_SS") (class "Default")
      (node (ref "CON_SPI") (pin "6") (pinfunction "6_6") (pintype "bidirectional"))
      (node (ref "U2") (pin "20") (pinfunction "PA4-SPI1NSS/DAC1/USART2CK/ADC4-SPI3NSS/I2S3WS_20") (pintype "bidirectional"))
    )
    (net (code "18") (name "GND") (class "Default")
      (node (ref "C1") (pin "P$2") (pinfunction "2_P$2") (pintype "passive"))
      (node (ref "C10") (pin "P$1") (pinfunction "1_P$1") (pintype "passive"))
      (node (ref "C101") (pin "P$2") (pinfunction "2_P$2") (pintype "passive"))
      (node (ref "C104") (pin "P$2") (pinfunction "2_P$2") (pintype "passive"))
      (node (ref "C105") (pin "P$2") (pinfunction "2_P$2") (pintype "passive"))
      (node (ref "C106") (pin "P$1") (pinfunction "1_P$1") (pintype "passive"))
      (node (ref "C108") (pin "P$2") (pinfunction "2_P$2") (pintype "passive"))
      (node (ref "C109") (pin "P$2") (pinfunction "2_P$2") (pintype "passive"))
      (node (ref "C11") (pin "P$1") (pinfunction "1_P$1") (pintype "passive"))
      (node (ref "C110") (pin "P$2") (pinfunction "2_P$2") (pintype "passive"))
      (node (ref "C112") (pin "P$2") (pinfunction "2_P$2") (pintype "passive"))
      (node (ref "C113") (pin "P$2") (pinfunction "2_P$2") (pintype "passive"))
      (node (ref "C12") (pin "P$1") (pinfunction "1_P$1") (pintype "passive"))
      (node (ref "C13") (pin "P$2") (pinfunction "2_P$2") (pintype "passive"))
      (node (ref "C14") (pin "P$1") (pinfunction "1_P$1") (pintype "passive"))
      (node (ref "C15") (pin "P$2") (pinfunction "2_P$2") (pintype "passive"))
      (node (ref "C2") (pin "P$2") (pinfunction "2_P$2") (pintype "passive"))
      (node (ref "C26") (pin "P$2") (pinfunction "2_P$2") (pintype "passive"))
      (node (ref "C27") (pin "P$1") (pinfunction "1_P$1") (pintype "passive"))
      (node (ref "C28") (pin "P$2") (pinfunction "2_P$2") (pintype "passive"))
      (node (ref "C3") (pin "P$2") (pinfunction "2_P$2") (pintype "passive"))
      (node (ref "C31") (pin "P$1") (pinfunction "1_P$1") (pintype "passive"))
      (node (ref "C35") (pin "P$2") (pinfunction "2_P$2") (pintype "passive"))
      (node (ref "C36") (pin "P$2") (pinfunction "2_P$2") (pintype "passive"))
      (node (ref "C37") (pin "-") (pinfunction "-_-") (pintype "passive"))
      (node (ref "C38") (pin "P$2") (pinfunction "2_P$2") (pintype "passive"))
      (node (ref "C39") (pin "-") (pinfunction "-_-") (pintype "passive"))
      (node (ref "C4") (pin "P$1") (pinfunction "1_P$1") (pintype "passive"))
      (node (ref "C42") (pin "P$1") (pinfunction "1_P$1") (pintype "passive"))
      (node (ref "C5") (pin "P$1") (pinfunction "1_P$1") (pintype "passive"))
      (node (ref "C6") (pin "P$2") (pinfunction "2_P$2") (pintype "passive"))
      (node (ref "C7") (pin "P$1") (pinfunction "1_P$1") (pintype "passive"))
      (node (ref "C9") (pin "P$2") (pinfunction "2_P$2") (pintype "passive"))
      (node (ref "CON_ANALOG1") (pin "1") (pinfunction "1_1") (pintype "bidirectional"))
      (node (ref "CON_CAN/I2C1") (pin "1") (pinfunction "1_1") (pintype "bidirectional"))
      (node (ref "CON_GPIO") (pin "1") (pinfunction "1_1") (pintype "bidirectional"))
      (node (ref "CON_I2C2") (pin "1") (pinfunction "1_1") (pintype "bidirectional"))
      (node (ref "CON_SPI") (pin "1") (pinfunction "1_1") (pintype "bidirectional"))
      (node (ref "CON_UART1/5") (pin "1") (pinfunction "1_1") (pintype "bidirectional"))
      (node (ref "CON_UART1/5") (pin "4") (pinfunction "4_4") (pintype "bidirectional"))
      (node (ref "CON_UART2") (pin "1") (pinfunction "1_1") (pintype "bidirectional"))
      (node (ref "CON_UART3") (pin "1") (pinfunction "1_1") (pintype "bidirectional"))
      (node (ref "CON_USB") (pin "4") (pinfunction "4_4") (pintype "bidirectional"))
      (node (ref "CON_USB_MICRO") (pin "PIN_5") (pinfunction "5_PIN_5") (pintype "input"))
      (node (ref "IC101") (pin "2") (pinfunction "GND_2") (pintype "power_in"))
      (node (ref "IC102") (pin "2") (pinfunction "PS_2") (pintype "bidirectional"))
      (node (ref "IC102") (pin "3") (pinfunction "GND_3") (pintype "bidirectional"))
      (node (ref "IC9") (pin "2") (pinfunction "GND_2") (pintype "bidirectional"))
      (node (ref "JP12") (pin "P$2") (pinfunction "2_P$2") (pintype "passive"))
      (node (ref "JP13") (pin "P$2") (pinfunction "2_P$2") (pintype "passive"))
      (node (ref "JTAG") (pin "3") (pinfunction "3_3") (pintype "bidirectional"))
      (node (ref "JTAG") (pin "5") (pinfunction "5_5") (pintype "bidirectional"))
      (node (ref "JTAG") (pin "7") (pinfunction "7_7") (pintype "bidirectional"))
      (node (ref "JTAG") (pin "9") (pinfunction "9_9") (pintype "bidirectional"))
      (node (ref "LEDVIN") (pin "C") (pinfunction "C_C") (pintype "passive"))
      (node (ref "LT_I2C2") (pin "1") (pinfunction "GND_1") (pintype "bidirectional"))
      (node (ref "PH1") (pin "3") (pinfunction "3_3") (pintype "bidirectional"))
      (node (ref "PH1") (pin "6") (pinfunction "3_6") (pintype "bidirectional"))
      (node (ref "PH2") (pin "3") (pinfunction "3_3") (pintype "bidirectional"))
      (node (ref "PH2") (pin "6") (pinfunction "3_6") (pintype "bidirectional"))
      (node (ref "PH3") (pin "3") (pinfunction "3_3") (pintype "bidirectional"))
      (node (ref "PH3") (pin "6") (pinfunction "3_6") (pintype "bidirectional"))
      (node (ref "PH4") (pin "3") (pinfunction "3_3") (pintype "bidirectional"))
      (node (ref "PH4") (pin "6") (pinfunction "3_6") (pintype "bidirectional"))
      (node (ref "Q1") (pin "P$2") (pinfunction "P$2_P$2") (pintype "bidirectional"))
      (node (ref "Q1") (pin "P$4") (pinfunction "P$4_P$4") (pintype "bidirectional"))
      (node (ref "R1") (pin "P$2") (pinfunction "2_P$2") (pintype "passive"))
      (node (ref "R18") (pin "P$2") (pinfunction "2_P$2") (pintype "passive"))
      (node (ref "R30") (pin "P$1") (pinfunction "1_P$1") (pintype "passive"))
      (node (ref "R55") (pin "P$1") (pinfunction "1_P$1") (pintype "passive"))
      (node (ref "R61") (pin "P$2") (pinfunction "2_P$2") (pintype "passive"))
      (node (ref "SW1") (pin "1") (pinfunction "1_1") (pintype "bidirectional"))
      (node (ref "SW1") (pin "G") (pinfunction "GND_G") (pintype "bidirectional"))
      (node (ref "U1") (pin "2") (pinfunction "VSS_2") (pintype "power_in"))
      (node (ref "U102") (pin "1") (pinfunction "CLKIN_1") (pintype "bidirectional"))
      (node (ref "U102") (pin "11") (pinfunction "FSYNC_11") (pintype "bidirectional"))
      (node (ref "U102") (pin "18") (pinfunction "GND_18") (pintype "bidirectional"))
      (node (ref "U103") (pin "11") (pinfunction "GND2_11") (pintype "bidirectional"))
      (node (ref "U103") (pin "9") (pinfunction "GND_9") (pintype "bidirectional"))
      (node (ref "U2") (pin "12") (pinfunction "VSSA_12") (pintype "power_in"))
      (node (ref "U2") (pin "18") (pinfunction "VSS4_18") (pintype "bidirectional"))
      (node (ref "U2") (pin "63") (pinfunction "VSS3_63") (pintype "power_in"))
      (node (ref "VREG1") (pin "5") (pinfunction "GND4_5") (pintype "bidirectional"))
      (node (ref "VREG1") (pin "6") (pinfunction "GND3_6") (pintype "bidirectional"))
      (node (ref "VREG1") (pin "7") (pinfunction "GND2_7") (pintype "bidirectional"))
      (node (ref "VREG1") (pin "8") (pinfunction "GND1_8") (pintype "bidirectional"))
    )
    (net (code "19") (name "I2C2_SCL") (class "Default")
      (node (ref "CON_I2C2") (pin "3") (pinfunction "3_3") (pintype "bidirectional"))
      (node (ref "R4") (pin "P$2") (pinfunction "2_P$2") (pintype "passive"))
      (node (ref "U2") (pin "29") (pinfunction "PB10-I2C2SCL/USART3TX/ETH_MII_RX_ER-TIM2CH3_29") (pintype "bidirectional"))
    )
    (net (code "20") (name "I2C2_SDA") (class "Default")
      (node (ref "CON_I2C2") (pin "4") (pinfunction "4_4") (pintype "bidirectional"))
      (node (ref "R5") (pin "P$2") (pinfunction "2_P$2") (pintype "passive"))
      (node (ref "U2") (pin "30") (pinfunction "PB11-I2C2SDA/USART3RX/ETH_(R)MII_TX_EN-TIM2CH4_30") (pintype "bidirectional"))
    )
    (net (code "21") (name "IMU+3V3") (class "Default")
      (node (ref "C105") (pin "P$1") (pinfunction "1_P$1") (pintype "passive"))
      (node (ref "C108") (pin "P$1") (pinfunction "1_P$1") (pintype "passive"))
      (node (ref "C112") (pin "P$1") (pinfunction "1_P$1") (pintype "passive"))
      (node (ref "IC101") (pin "5") (pinfunction "OUT_5") (pintype "output"))
      (node (ref "L101") (pin "P$2") (pinfunction "2_P$2") (pintype "passive"))
      (node (ref "U102") (pin "13") (pinfunction "VDD_13") (pintype "bidirectional"))
      (node (ref "U103") (pin "13") (pinfunction "VDDIO_13") (pintype "bidirectional"))
      (node (ref "U103") (pin "2") (pinfunction "VDD_2") (pintype "bidirectional"))
      (node (ref "U103") (pin "4") (pinfunction "S1_4") (pintype "bidirectional"))
    )
    (net (code "22") (name "IMU_BARO_CS") (class "Default")
      (node (ref "IC102") (pin "4") (pinfunction "~{CSB}_4") (pintype "bidirectional"))
      (node (ref "IC102") (pin "5") (pinfunction "~{CSB}_5") (pintype "bidirectional"))
      (node (ref "U2") (pin "2") (pinfunction "PC13-TAMPER-RTC_2") (pintype "bidirectional"))
    )
    (net (code "23") (name "IMU_MAG_INT") (class "Default")
      (node (ref "U103") (pin "15") (pinfunction "DRDY_15") (pintype "bidirectional"))
      (node (ref "U2") (pin "3") (pinfunction "PC14-OSC32_IN_3") (pintype "bidirectional"))
    )
    (net (code "24") (name "IMU_MPU_CS") (class "Default")
      (node (ref "U102") (pin "8") (pinfunction "~{CS}_8") (pintype "bidirectional"))
      (node (ref "U2") (pin "33") (pinfunction "PB12-SPI2NSS/I2S2WS/I2C2SMBA/USART3CK/TIM1BKIN/CAN2RX/ETH_(R)MII_TXD0_33") (pintype "bidirectional"))
    )
    (net (code "25") (name "IMU_MPU_INT") (class "Default")
      (node (ref "R29") (pin "P$2") (pinfunction "2_P$2") (pintype "passive"))
      (node (ref "U102") (pin "12") (pinfunction "INT_12") (pintype "bidirectional"))
      (node (ref "U2") (pin "57") (pinfunction "PB5-I2C1SMBA/SPI3MOSI/ETH_(R)MII_PPS_OUT/I2S3SD-TIM3CH2/SPI1MOSI/CAN2RX_57") (pintype "bidirectional"))
    )
    (net (code "26") (name "IMU_SPI_MISO") (class "Default")
      (node (ref "IC102") (pin "6") (pinfunction "SDO_6") (pintype "bidirectional"))
      (node (ref "U102") (pin "9") (pinfunction "AD0/SDO_9") (pintype "bidirectional"))
      (node (ref "U2") (pin "35") (pinfunction "PB14-SPI2MISO/USART3RTS/TIM1CH2N_35") (pintype "bidirectional"))
    )
    (net (code "27") (name "IMU_SPI_MOSI") (class "Default")
      (node (ref "IC102") (pin "7") (pinfunction "SDI/SDA_7") (pintype "bidirectional"))
      (node (ref "U102") (pin "24") (pinfunction "SDA/SDI_24") (pintype "bidirectional"))
      (node (ref "U2") (pin "36") (pinfunction "PB15-SPI2MOSI/I2S2SD/TIM1CH3N_36") (pintype "bidirectional"))
    )
    (net (code "28") (name "IMU_SPI_SCK") (class "Default")
      (node (ref "IC102") (pin "8") (pinfunction "SCLK_8") (pintype "bidirectional"))
      (node (ref "U102") (pin "23") (pinfunction "SCL/SCLK_23") (pintype "bidirectional"))
      (node (ref "U2") (pin "34") (pinfunction "PB13-SPI2SCK/I2S2CK/USART3CTS/TIM1CH1N/CAN2TX/ETH_(R)MII_TXD1_34") (pintype "bidirectional"))
    )
    (net (code "29") (name "JTAG_RST") (class "Default")
      (node (ref "C27") (pin "P$2") (pinfunction "2_P$2") (pintype "passive"))
      (node (ref "JTAG") (pin "10") (pinfunction "10_10") (pintype "bidirectional"))
      (node (ref "R7") (pin "P$1") (pinfunction "1_P$1") (pintype "passive"))
      (node (ref "U2") (pin "7") (pinfunction "NRST_7") (pintype "bidirectional"))
    )
    (net (code "30") (name "JTAG_TCK") (class "Default")
      (node (ref "JTAG") (pin "4") (pinfunction "4_4") (pintype "bidirectional"))
      (node (ref "U2") (pin "49") (pinfunction "PA14/JTCK/SWCLK_49") (pintype "bidirectional"))
    )
    (net (code "31") (name "JTAG_TDI") (class "Default")
      (node (ref "JTAG") (pin "8") (pinfunction "8_8") (pintype "bidirectional"))
      (node (ref "U2") (pin "50") (pinfunction "PA15/JTDI-SPI3NSS/I2S3WS-TIM2CH1ETR/SPI1NSS_50") (pintype "bidirectional"))
    )
    (net (code "32") (name "JTAG_TDO") (class "Default")
      (node (ref "JTAG") (pin "6") (pinfunction "6_6") (pintype "bidirectional"))
      (node (ref "U2") (pin "55") (pinfunction "PB3/JTDO-SPI3SCK/I2S3CK-TIM2CH2/TRACESWO/SPI1SCK_55") (pintype "bidirectional"))
    )
    (net (code "33") (name "JTAG_TMS") (class "Default")
      (node (ref "JTAG") (pin "2") (pinfunction "2_2") (pintype "bidirectional"))
      (node (ref "U2") (pin "46") (pinfunction "PA13/JTMS/SWDIO_46") (pintype "bidirectional"))
    )
    (net (code "34") (name "LED1") (class "Default")
      (node (ref "LED1") (pin "C") (pinfunction "C_C") (pintype "passive"))
      (node (ref "U2") (pin "41") (pinfunction "PA8-USART1CK/OTG_FS_SOF/MCO/TIM1CH1_41") (pintype "bidirectional"))
    )
    (net (code "35") (name "LED2") (class "Default")
      (node (ref "CON_GPIO") (pin "4") (pinfunction "4_4") (pintype "bidirectional"))
      (node (ref "LED2") (pin "C") (pinfunction "C_C") (pintype "passive"))
      (node (ref "U2") (pin "56") (pinfunction "PB4/JNTRST-SPI3MISO-TIM3CH1/SPI1MISO_56") (pintype "bidirectional"))
    )
    (net (code "36") (name "LED3") (class "Default")
      (node (ref "LED3") (pin "C") (pinfunction "C_C") (pintype "passive"))
      (node (ref "U2") (pin "10") (pinfunction "PC2-ADC12/ETH_MII_TXD2_10") (pintype "bidirectional"))
    )
    (net (code "37") (name "LED4") (class "Default")
      (node (ref "LED4") (pin "C") (pinfunction "C_C") (pintype "passive"))
      (node (ref "U2") (pin "25") (pinfunction "PC5-ADC15ETH_(R)MII_RXD1_25") (pintype "bidirectional"))
    )
    (net (code "38") (name "LED5") (class "Default")
      (node (ref "LED5") (pin "C") (pinfunction "C_C") (pintype "passive"))
      (node (ref "U2") (pin "4") (pinfunction "PC15-OSC32_OUT_4") (pintype "bidirectional"))
    )
    (net (code "39") (name "LT_I2C1_SCL") (class "Default")
      (node (ref "CON_CAN/I2C1") (pin "6") (pinfunction "6_6") (pintype "bidirectional"))
      (node (ref "JP10") (pin "P$2") (pinfunction "2_P$2") (pintype "passive"))
      (node (ref "LT_I2C2") (pin "6") (pinfunction "SCL2_6") (pintype "bidirectional"))
      (node (ref "R44") (pin "P$1") (pinfunction "1_P$1") (pintype "passive"))
    )
    (net (code "40") (name "LT_I2C1_SDA") (class "Default")
      (node (ref "CON_CAN/I2C1") (pin "7") (pinfunction "7_7") (pintype "bidirectional"))
      (node (ref "JP11") (pin "P$2") (pinfunction "2_P$2") (pintype "passive"))
      (node (ref "LT_I2C2") (pin "5") (pinfunction "SDA2_5") (pintype "bidirectional"))
      (node (ref "R43") (pin "P$1") (pinfunction "1_P$1") (pintype "passive"))
    )
    (net (code "41") (name "Net-(C13-1)") (class "Default")
      (node (ref "C13") (pin "P$1") (pinfunction "1_P$1") (pintype "passive"))
      (node (ref "IC9") (pin "4") (pinfunction "BYPASS_4") (pintype "bidirectional"))
    )
    (net (code "42") (name "Net-(C15-1)") (class "Default")
      (node (ref "C15") (pin "P$1") (pinfunction "1_P$1") (pintype "passive"))
      (node (ref "LT_I2C2") (pin "7") (pinfunction "VREF2_7") (pintype "bidirectional"))
      (node (ref "LT_I2C2") (pin "8") (pinfunction "EN_8") (pintype "bidirectional"))
      (node (ref "R25") (pin "P$1") (pinfunction "1_P$1") (pintype "passive"))
    )
    (net (code "43") (name "Net-(C28-1)") (class "Default")
      (node (ref "C28") (pin "P$1") (pinfunction "1_P$1") (pintype "passive"))
      (node (ref "C31") (pin "P$2") (pinfunction "2_P$2") (pintype "passive"))
      (node (ref "L1") (pin "P$2") (pinfunction "2_P$2") (pintype "passive"))
      (node (ref "U2") (pin "13") (pinfunction "VDDA_13") (pintype "power_in"))
    )
    (net (code "44") (name "Net-(C35-1)") (class "Default")
      (node (ref "C35") (pin "P$1") (pinfunction "1_P$1") (pintype "passive"))
      (node (ref "VREG1") (pin "4") (pinfunction "BYP_4") (pintype "bidirectional"))
    )
    (net (code "45") (name "Net-(C42-2)") (class "Default")
      (node (ref "C42") (pin "P$2") (pinfunction "2_P$2") (pintype "passive"))
      (node (ref "R58") (pin "P$2") (pinfunction "2_P$2") (pintype "passive"))
      (node (ref "R59") (pin "P$1") (pinfunction "1_P$1") (pintype "passive"))
      (node (ref "R60") (pin "P$2") (pinfunction "2_P$2") (pintype "passive"))
      (node (ref "R61") (pin "P$1") (pinfunction "1_P$1") (pintype "passive"))
    )
    (net (code "46") (name "Net-(C101-1)") (class "Default")
      (node (ref "C101") (pin "P$1") (pinfunction "1_P$1") (pintype "passive"))
      (node (ref "IC102") (pin "1") (pinfunction "VDD_1") (pintype "bidirectional"))
      (node (ref "L101") (pin "P$1") (pinfunction "1_P$1") (pintype "passive"))
    )
    (net (code "47") (name "Net-(C106-2)") (class "Default")
      (node (ref "C106") (pin "P$2") (pinfunction "2_P$2") (pintype "passive"))
      (node (ref "IC101") (pin "4") (pinfunction "ADJ_4") (pintype "passive"))
    )
    (net (code "48") (name "Net-(C109-1)") (class "Default")
      (node (ref "C109") (pin "P$1") (pinfunction "1_P$1") (pintype "passive"))
      (node (ref "U102") (pin "20") (pinfunction "CPOUT_20") (pintype "bidirectional"))
    )
    (net (code "49") (name "Net-(C110-1)") (class "Default")
      (node (ref "C110") (pin "P$1") (pinfunction "1_P$1") (pintype "passive"))
      (node (ref "U102") (pin "10") (pinfunction "REGOUT_10") (pintype "bidirectional"))
    )
    (net (code "50") (name "Net-(C113-1)") (class "Default")
      (node (ref "C113") (pin "P$1") (pinfunction "1_P$1") (pintype "passive"))
      (node (ref "U103") (pin "10") (pinfunction "C1_10") (pintype "bidirectional"))
    )
    (net (code "51") (name "Net-(C114-1)") (class "Default")
      (node (ref "C114") (pin "P$1") (pinfunction "1_P$1") (pintype "passive"))
      (node (ref "U103") (pin "12") (pinfunction "SETC_12") (pintype "bidirectional"))
    )
    (net (code "52") (name "Net-(C114-2)") (class "Default")
      (node (ref "C114") (pin "P$2") (pinfunction "2_P$2") (pintype "passive"))
      (node (ref "U103") (pin "8") (pinfunction "SETP_8") (pintype "bidirectional"))
    )
    (net (code "53") (name "Net-(R8-1)") (class "Default")
      (node (ref "LED2") (pin "A") (pinfunction "A_A") (pintype "passive"))
      (node (ref "R8") (pin "P$1") (pinfunction "1_P$1") (pintype "passive"))
    )
    (net (code "54") (name "Net-(R10-1)") (class "Default")
      (node (ref "LED1") (pin "A") (pinfunction "A_A") (pintype "passive"))
      (node (ref "R10") (pin "P$1") (pinfunction "1_P$1") (pintype "passive"))
    )
    (net (code "55") (name "Net-(R12-1)") (class "Default")
      (node (ref "LED5") (pin "A") (pinfunction "A_A") (pintype "passive"))
      (node (ref "R12") (pin "P$1") (pinfunction "1_P$1") (pintype "passive"))
    )
    (net (code "56") (name "Net-(R23-1)") (class "Default")
      (node (ref "LEDVIN") (pin "A") (pinfunction "A_A") (pintype "passive"))
      (node (ref "R23") (pin "P$1") (pinfunction "1_P$1") (pintype "passive"))
    )
    (net (code "57") (name "Net-(R37-1)") (class "Default")
      (node (ref "LED4") (pin "A") (pinfunction "A_A") (pintype "passive"))
      (node (ref "R37") (pin "P$1") (pinfunction "1_P$1") (pintype "passive"))
    )
    (net (code "58") (name "Net-(R38-1)") (class "Default")
      (node (ref "LED3") (pin "A") (pinfunction "A_A") (pintype "passive"))
      (node (ref "R38") (pin "P$1") (pinfunction "1_P$1") (pintype "passive"))
    )
    (net (code "59") (name "Net-(R55-2)") (class "Default")
      (node (ref "R55") (pin "P$2") (pinfunction "2_P$2") (pintype "passive"))
      (node (ref "R56") (pin "P$1") (pinfunction "1_P$1") (pintype "passive"))
      (node (ref "U1") (pin "8") (pinfunction "RS_8") (pintype "input"))
    )
    (net (code "60") (name "OSC_IN") (class "Default")
      (node (ref "C4") (pin "P$2") (pinfunction "2_P$2") (pintype "passive"))
      (node (ref "Q1") (pin "P$3") (pinfunction "P$3_P$3") (pintype "bidirectional"))
      (node (ref "U2") (pin "5") (pinfunction "PD0-OSC_IN-CAN1RX_5") (pintype "input"))
    )
    (net (code "61") (name "OSC_OUT") (class "Default")
      (node (ref "C6") (pin "P$1") (pinfunction "1_P$1") (pintype "passive"))
      (node (ref "Q1") (pin "P$1") (pinfunction "P$1_P$1") (pintype "bidirectional"))
      (node (ref "U2") (pin "6") (pinfunction "PD1-OSC_OUT-CAN1TX_6") (pintype "output"))
    )
    (net (code "62") (name "PC12") (class "Default")
      (node (ref "CON_GPIO") (pin "3") (pinfunction "3_3") (pintype "bidirectional"))
      (node (ref "U2") (pin "53") (pinfunction "PC12-USART5TX-USART3CK/SPI3MOSI/I2S3SD_53") (pintype "bidirectional"))
    )
    (net (code "63") (name "S1") (class "Default")
      (node (ref "PH1") (pin "1") (pinfunction "1_1") (pintype "bidirectional"))
      (node (ref "R41") (pin "P$1") (pinfunction "1_P$1") (pintype "passive"))
    )
    (net (code "64") (name "S2") (class "Default")
      (node (ref "PH1") (pin "4") (pinfunction "1_4") (pintype "bidirectional"))
      (node (ref "R42") (pin "P$1") (pinfunction "1_P$1") (pintype "passive"))
    )
    (net (code "65") (name "S3") (class "Default")
      (node (ref "PH2") (pin "1") (pinfunction "1_1") (pintype "bidirectional"))
      (node (ref "R45") (pin "P$1") (pinfunction "1_P$1") (pintype "passive"))
    )
    (net (code "66") (name "S4") (class "Default")
      (node (ref "PH2") (pin "4") (pinfunction "1_4") (pintype "bidirectional"))
      (node (ref "R27") (pin "P$1") (pinfunction "1_P$1") (pintype "passive"))
    )
    (net (code "67") (name "S5") (class "Default")
      (node (ref "PH3") (pin "1") (pinfunction "1_1") (pintype "bidirectional"))
      (node (ref "R28") (pin "P$1") (pinfunction "1_P$1") (pintype "passive"))
    )
    (net (code "68") (name "S6") (class "Default")
      (node (ref "PH3") (pin "4") (pinfunction "1_4") (pintype "bidirectional"))
      (node (ref "R31") (pin "P$1") (pinfunction "1_P$1") (pintype "passive"))
    )
    (net (code "69") (name "S7") (class "Default")
      (node (ref "PH4") (pin "1") (pinfunction "1_1") (pintype "bidirectional"))
      (node (ref "R39") (pin "P$1") (pinfunction "1_P$1") (pintype "passive"))
    )
    (net (code "70") (name "S8") (class "Default")
      (node (ref "PH4") (pin "4") (pinfunction "1_4") (pintype "bidirectional"))
      (node (ref "R40") (pin "P$1") (pinfunction "1_P$1") (pintype "passive"))
    )
    (net (code "71") (name "SCL") (class "Default")
      (node (ref "R9") (pin "P$1") (pinfunction "1_P$1") (pintype "passive"))
      (node (ref "U102") (pin "7") (pinfunction "AUX_CL_7") (pintype "bidirectional"))
      (node (ref "U103") (pin "1") (pinfunction "SCL_1") (pintype "bidirectional"))
    )
    (net (code "72") (name "SDA") (class "Default")
      (node (ref "R2") (pin "P$1") (pinfunction "1_P$1") (pintype "passive"))
      (node (ref "U102") (pin "6") (pinfunction "AUX_DA_6") (pintype "bidirectional"))
      (node (ref "U103") (pin "16") (pinfunction "SDA_16") (pintype "bidirectional"))
    )
    (net (code "73") (name "SERVO_1") (class "Default")
      (node (ref "R41") (pin "P$2") (pinfunction "2_P$2") (pintype "passive"))
      (node (ref "U2") (pin "37") (pinfunction "PC6-I2S2MCK-TIM3CH1_37") (pintype "bidirectional"))
    )
    (net (code "74") (name "SERVO_2") (class "Default")
      (node (ref "R42") (pin "P$2") (pinfunction "2_P$2") (pintype "passive"))
      (node (ref "U2") (pin "38") (pinfunction "PC7-I2S3MCK-TIM3CH2_38") (pintype "bidirectional"))
    )
    (net (code "75") (name "SERVO_3") (class "Default")
      (node (ref "R45") (pin "P$2") (pinfunction "2_P$2") (pintype "passive"))
      (node (ref "U2") (pin "39") (pinfunction "PC8-TIM3CH3_39") (pintype "bidirectional"))
    )
    (net (code "76") (name "SERVO_4") (class "Default")
      (node (ref "R27") (pin "P$2") (pinfunction "2_P$2") (pintype "passive"))
      (node (ref "U2") (pin "40") (pinfunction "PC9-TIM3CH4_40") (pintype "bidirectional"))
    )
    (net (code "77") (name "SERVO_5") (class "Default")
      (node (ref "R28") (pin "P$2") (pinfunction "2_P$2") (pintype "passive"))
      (node (ref "U2") (pin "14") (pinfunction "PA0-WKUP/USART2CTS/ADC0/TIM2CH1ETR/TIM5CH1/ETH_MII_CRS_WKUP_14") (pintype "bidirectional"))
    )
    (net (code "78") (name "SERVO_6") (class "Default")
      (node (ref "R31") (pin "P$2") (pinfunction "2_P$2") (pintype "passive"))
      (node (ref "U2") (pin "15") (pinfunction "PA1-USART2RTS/ADC1/TIM5CH2/TIM2CH2/ETH_MII_RX_CLK/ETH_RMII_REF_CLK_15") (pintype "bidirectional"))
    )
    (net (code "79") (name "SERVO_7{slash}I2C1_SCL") (class "Default")
      (node (ref "JP10") (pin "P$1") (pinfunction "1_P$1") (pintype "passive"))
      (node (ref "LT_I2C2") (pin "3") (pinfunction "SCL1_3") (pintype "bidirectional"))
      (node (ref "R33") (pin "P$1") (pinfunction "1_P$1") (pintype "passive"))
      (node (ref "R39") (pin "P$2") (pinfunction "2_P$2") (pintype "passive"))
      (node (ref "U2") (pin "58") (pinfunction "PB6-I2C1SCL/TIM4CH1-USART1TX/CAN2TX_58") (pintype "bidirectional"))
    )
    (net (code "80") (name "SERVO_8{slash}I2C1_SDA") (class "Default")
      (node (ref "JP11") (pin "P$1") (pinfunction "1_P$1") (pintype "passive"))
      (node (ref "LT_I2C2") (pin "4") (pinfunction "SDA1_4") (pintype "bidirectional"))
      (node (ref "R34") (pin "P$1") (pinfunction "1_P$1") (pintype "passive"))
      (node (ref "R40") (pin "P$2") (pinfunction "2_P$2") (pintype "passive"))
      (node (ref "U2") (pin "59") (pinfunction "PB7-I2C1SDA/TIM4CH2-USART1RX_59") (pintype "bidirectional"))
    )
    (net (code "81") (name "SERVO_BUS") (class "Default")
      (node (ref "JP1") (pin "P$1") (pinfunction "1_P$1") (pintype "passive"))
      (node (ref "PH1") (pin "2") (pinfunction "2_2") (pintype "bidirectional"))
      (node (ref "PH1") (pin "5") (pinfunction "2_5") (pintype "bidirectional"))
      (node (ref "PH2") (pin "2") (pinfunction "2_2") (pintype "bidirectional"))
      (node (ref "PH2") (pin "5") (pinfunction "2_5") (pintype "bidirectional"))
      (node (ref "PH3") (pin "2") (pinfunction "2_2") (pintype "bidirectional"))
      (node (ref "PH3") (pin "5") (pinfunction "2_5") (pintype "bidirectional"))
      (node (ref "PH4") (pin "2") (pinfunction "2_2") (pintype "bidirectional"))
      (node (ref "PH4") (pin "5") (pinfunction "2_5") (pintype "bidirectional"))
    )
    (net (code "82") (name "U1_U5_POW") (class "Default")
      (node (ref "CON_UART1/5") (pin "2") (pinfunction "2_2") (pintype "bidirectional"))
      (node (ref "CON_UART1/5") (pin "5") (pinfunction "5_5") (pintype "bidirectional"))
      (node (ref "JP8") (pin "P$2") (pinfunction "2_P$2") (pintype "passive"))
      (node (ref "JP9") (pin "P$2") (pinfunction "2_P$2") (pintype "passive"))
      (node (ref "R24") (pin "P$1") (pinfunction "1_P$1") (pintype "passive"))
      (node (ref "R6") (pin "P$1") (pinfunction "1_P$1") (pintype "passive"))
    )
    (net (code "83") (name "U3_POW") (class "Default")
      (node (ref "CON_UART3") (pin "2") (pinfunction "2_2") (pintype "bidirectional"))
      (node (ref "JP6") (pin "P$2") (pinfunction "2_P$2") (pintype "passive"))
      (node (ref "JP7") (pin "P$2") (pinfunction "2_P$2") (pintype "passive"))
      (node (ref "R3") (pin "P$1") (pinfunction "1_P$1") (pintype "passive"))
    )
    (net (code "84") (name "UART1_RX") (class "Default")
      (node (ref "CON_UART1/5") (pin "3") (pinfunction "3_3") (pintype "bidirectional"))
      (node (ref "R24") (pin "P$2") (pinfunction "2_P$2") (pintype "passive"))
      (node (ref "U2") (pin "43") (pinfunction "PA10-USART1RX/TIM1CH3/OTG_FS_ID_43") (pintype "bidirectional"))
    )
    (net (code "85") (name "UART2_RX") (class "Default")
      (node (ref "CON_UART2") (pin "4") (pinfunction "4_4") (pintype "bidirectional"))
      (node (ref "R26") (pin "P$2") (pinfunction "2_P$2") (pintype "passive"))
      (node (ref "U2") (pin "17") (pinfunction "PA3-USART2RX/TIM5CH4/ADC3/TIM2CH4/ETH_MII_COL_17") (pintype "bidirectional"))
    )
    (net (code "86") (name "UART2_TX") (class "Default")
      (node (ref "CON_UART2") (pin "3") (pinfunction "3_3") (pintype "bidirectional"))
      (node (ref "U2") (pin "16") (pinfunction "PA2-USART2TX/TIM5CH3/ADC2/TIM2CH3/ETH_(R)MII_MDIO_16") (pintype "bidirectional"))
    )
    (net (code "87") (name "UART3_RX") (class "Default")
      (node (ref "CON_UART3") (pin "4") (pinfunction "4_4") (pintype "bidirectional"))
      (node (ref "R3") (pin "P$2") (pinfunction "2_P$2") (pintype "passive"))
      (node (ref "U2") (pin "52") (pinfunction "PC11-USART4RX-USART3RX/SPI3MISO_52") (pintype "bidirectional"))
    )
    (net (code "88") (name "UART3_TX") (class "Default")
      (node (ref "CON_UART3") (pin "3") (pinfunction "3_3") (pintype "bidirectional"))
      (node (ref "U2") (pin "51") (pinfunction "PC10-USART4TX-USART3TX/SPI3SCK/I2S3CK_51") (pintype "bidirectional"))
    )
    (net (code "89") (name "UART5_RX") (class "Default")
      (node (ref "CON_UART1/5") (pin "6") (pinfunction "6_6") (pintype "bidirectional"))
      (node (ref "R6") (pin "P$2") (pinfunction "2_P$2") (pintype "passive"))
      (node (ref "U2") (pin "54") (pinfunction "PD2-TIM3ETR/USART5RX_54") (pintype "bidirectional"))
    )
    (net (code "90") (name "USB_DM") (class "Default")
      (node (ref "CON_USB") (pin "2") (pinfunction "2_2") (pintype "bidirectional"))
      (node (ref "CON_USB_MICRO") (pin "PIN_2") (pinfunction "2_PIN_2") (pintype "input"))
      (node (ref "U2") (pin "44") (pinfunction "PA11-USART1CTS/CAN1RX/OTG_FS_DM/TIM1CH4_44") (pintype "bidirectional"))
    )
    (net (code "91") (name "USB_DP") (class "Default")
      (node (ref "CON_USB") (pin "3") (pinfunction "3_3") (pintype "bidirectional"))
      (node (ref "CON_USB_MICRO") (pin "PIN_3") (pinfunction "3_PIN_3") (pintype "input"))
      (node (ref "U2") (pin "45") (pinfunction "PA12-USART1RTS/CAN1TX/OTG_FS_DP/TIM1ETR_45") (pintype "bidirectional"))
    )
    (net (code "92") (name "USB_VBUS") (class "Default")
      (node (ref "CON_USB") (pin "1") (pinfunction "1_1") (pintype "bidirectional"))
      (node (ref "CON_USB_MICRO") (pin "PIN_1") (pinfunction "1_PIN_1") (pintype "input"))
      (node (ref "D3") (pin "A") (pinfunction "A_A") (pintype "passive"))
      (node (ref "R1") (pin "P$1") (pinfunction "1_P$1") (pintype "passive"))
      (node (ref "U2") (pin "42") (pinfunction "PA9-USART1TX/TIM1CH2/OTG_FS_VBUS_42") (pintype "bidirectional"))
    )
    (net (code "93") (name "VREF") (class "Default")
      (node (ref "U1") (pin "5") (pinfunction "VREF_5") (pintype "power_in"))
    )
    (net (code "94") (name "VSS1") (class "Default")
      (node (ref "C7") (pin "P$2") (pinfunction "2_P$2") (pintype "passive"))
      (node (ref "JP12") (pin "P$1") (pinfunction "1_P$1") (pintype "passive"))
      (node (ref "U2") (pin "31") (pinfunction "VSS1_31") (pintype "power_in"))
    )
    (net (code "95") (name "VSS2") (class "Default")
      (node (ref "C14") (pin "P$2") (pinfunction "2_P$2") (pintype "passive"))
      (node (ref "JP13") (pin "P$1") (pinfunction "1_P$1") (pintype "passive"))
      (node (ref "U2") (pin "47") (pinfunction "VSS2_47") (pintype "power_in"))
    )
    (net (code "96") (name "V_BAT") (class "Default")
      (node (ref "CON_CAN/I2C1") (pin "2") (pinfunction "2_2") (pintype "bidirectional"))
      (node (ref "JP2") (pin "P$2") (pinfunction "2_P$2") (pintype "passive"))
      (node (ref "R17") (pin "P$1") (pinfunction "1_P$1") (pintype "passive"))
    )
    (net (code "97") (name "V_BAT_MEAS") (class "Default")
      (node (ref "R17") (pin "P$2") (pinfunction "2_P$2") (pintype "passive"))
      (node (ref "R18") (pin "P$1") (pinfunction "1_P$1") (pintype "passive"))
      (node (ref "U2") (pin "24") (pinfunction "PC4-ADC14/ETH_(R)MII_RXD0_24") (pintype "bidirectional"))
    )
    (net (code "98") (name "V_IN") (class "Default")
      (node (ref "C104") (pin "P$1") (pinfunction "1_P$1") (pintype "passive"))
      (node (ref "C3") (pin "P$1") (pinfunction "1_P$1") (pintype "passive"))
      (node (ref "C38") (pin "P$1") (pinfunction "1_P$1") (pintype "passive"))
      (node (ref "C39") (pin "+") (pinfunction "+_+") (pintype "passive"))
      (node (ref "CON_CAN/I2C1") (pin "3") (pinfunction "3_3") (pintype "bidirectional"))
      (node (ref "D3") (pin "C") (pinfunction "C_C") (pintype "passive"))
      (node (ref "IC101") (pin "1") (pinfunction "IN_1") (pintype "input"))
      (node (ref "IC101") (pin "3") (pinfunction "EN_3") (pintype "input"))
      (node (ref "IC9") (pin "1") (pinfunction "VIN_1") (pintype "bidirectional"))
      (node (ref "IC9") (pin "3") (pinfunction "ON/OFF_3") (pintype "bidirectional"))
      (node (ref "JP1") (pin "P$2") (pinfunction "2_P$2") (pintype "passive"))
      (node (ref "JP2") (pin "P$1") (pinfunction "1_P$1") (pintype "passive"))
      (node (ref "JP3") (pin "P$1") (pinfunction "1_P$1") (pintype "passive"))
      (node (ref "JP6") (pin "P$1") (pinfunction "1_P$1") (pintype "passive"))
      (node (ref "JP8") (pin "P$1") (pinfunction "1_P$1") (pintype "passive"))
      (node (ref "R23") (pin "P$2") (pinfunction "2_P$2") (pintype "passive"))
      (node (ref "VREG1") (pin "1") (pinfunction "ENABLE_1") (pintype "bidirectional"))
      (node (ref "VREG1") (pin "2") (pinfunction "VIN_2") (pintype "bidirectional"))
    )
    (net (code "99") (name "unconnected-(CON_USB_MICRO-4-PadPIN_4)") (class "Default")
      (node (ref "CON_USB_MICRO") (pin "PIN_4") (pinfunction "4_PIN_4") (pintype "input"))
    )
    (net (code "100") (name "unconnected-(CON_USB_MICRO-S1-PadGND_LEFT)") (class "Default")
      (node (ref "CON_USB_MICRO") (pin "GND_LEFT") (pinfunction "S1_GND_LEFT") (pintype "passive"))
    )
    (net (code "101") (name "unconnected-(CON_USB_MICRO-S2-PadGND_RIGHT)") (class "Default")
      (node (ref "CON_USB_MICRO") (pin "GND_RIGHT") (pinfunction "S2_GND_RIGHT") (pintype "passive"))
    )
    (net (code "102") (name "unconnected-(CON_USB_MICRO-S3-PadGND_UP_LEFT)") (class "Default")
      (node (ref "CON_USB_MICRO") (pin "GND_UP_LEFT") (pinfunction "S3_GND_UP_LEFT") (pintype "passive"))
    )
    (net (code "103") (name "unconnected-(CON_USB_MICRO-S4-PadGND_UP_RIGHT)") (class "Default")
      (node (ref "CON_USB_MICRO") (pin "GND_UP_RIGHT") (pinfunction "S4_GND_UP_RIGHT") (pintype "passive"))
    )
    (net (code "104") (name "unconnected-(U102-CKOUT-Pad22)") (class "Default")
      (node (ref "U102") (pin "22") (pinfunction "CKOUT_22") (pintype "bidirectional"))
    )
    (net (code "105") (name "unconnected-(U102-NC-Pad2)") (class "Default")
      (node (ref "U102") (pin "2") (pinfunction "NC_2") (pintype "bidirectional"))
    )
    (net (code "106") (name "unconnected-(U102-NC-Pad3)") (class "Default")
      (node (ref "U102") (pin "3") (pinfunction "NC_3") (pintype "bidirectional"))
    )
    (net (code "107") (name "unconnected-(U102-NC-Pad4)") (class "Default")
      (node (ref "U102") (pin "4") (pinfunction "NC_4") (pintype "bidirectional"))
    )
    (net (code "108") (name "unconnected-(U102-NC-Pad5)") (class "Default")
      (node (ref "U102") (pin "5") (pinfunction "NC_5") (pintype "bidirectional"))
    )
    (net (code "109") (name "unconnected-(U102-NC-Pad14)") (class "Default")
      (node (ref "U102") (pin "14") (pinfunction "NC_14") (pintype "bidirectional"))
    )
    (net (code "110") (name "unconnected-(U102-NC-Pad15)") (class "Default")
      (node (ref "U102") (pin "15") (pinfunction "NC_15") (pintype "bidirectional"))
    )
    (net (code "111") (name "unconnected-(U102-NC-Pad16)") (class "Default")
      (node (ref "U102") (pin "16") (pinfunction "NC_16") (pintype "bidirectional"))
    )
    (net (code "112") (name "unconnected-(U102-NC-Pad17)") (class "Default")
      (node (ref "U102") (pin "17") (pinfunction "NC_17") (pintype "bidirectional"))
    )
    (net (code "113") (name "unconnected-(U102-RESV-Pad19)") (class "Default")
      (node (ref "U102") (pin "19") (pinfunction "RESV_19") (pintype "bidirectional"))
    )
    (net (code "114") (name "unconnected-(U102-RESV-Pad21)") (class "Default")
      (node (ref "U102") (pin "21") (pinfunction "RESV_21") (pintype "bidirectional"))
    )
  )
)
